# Debugging_board.net
KiCad netlist of a schematic drawn in EasyEDA Pro
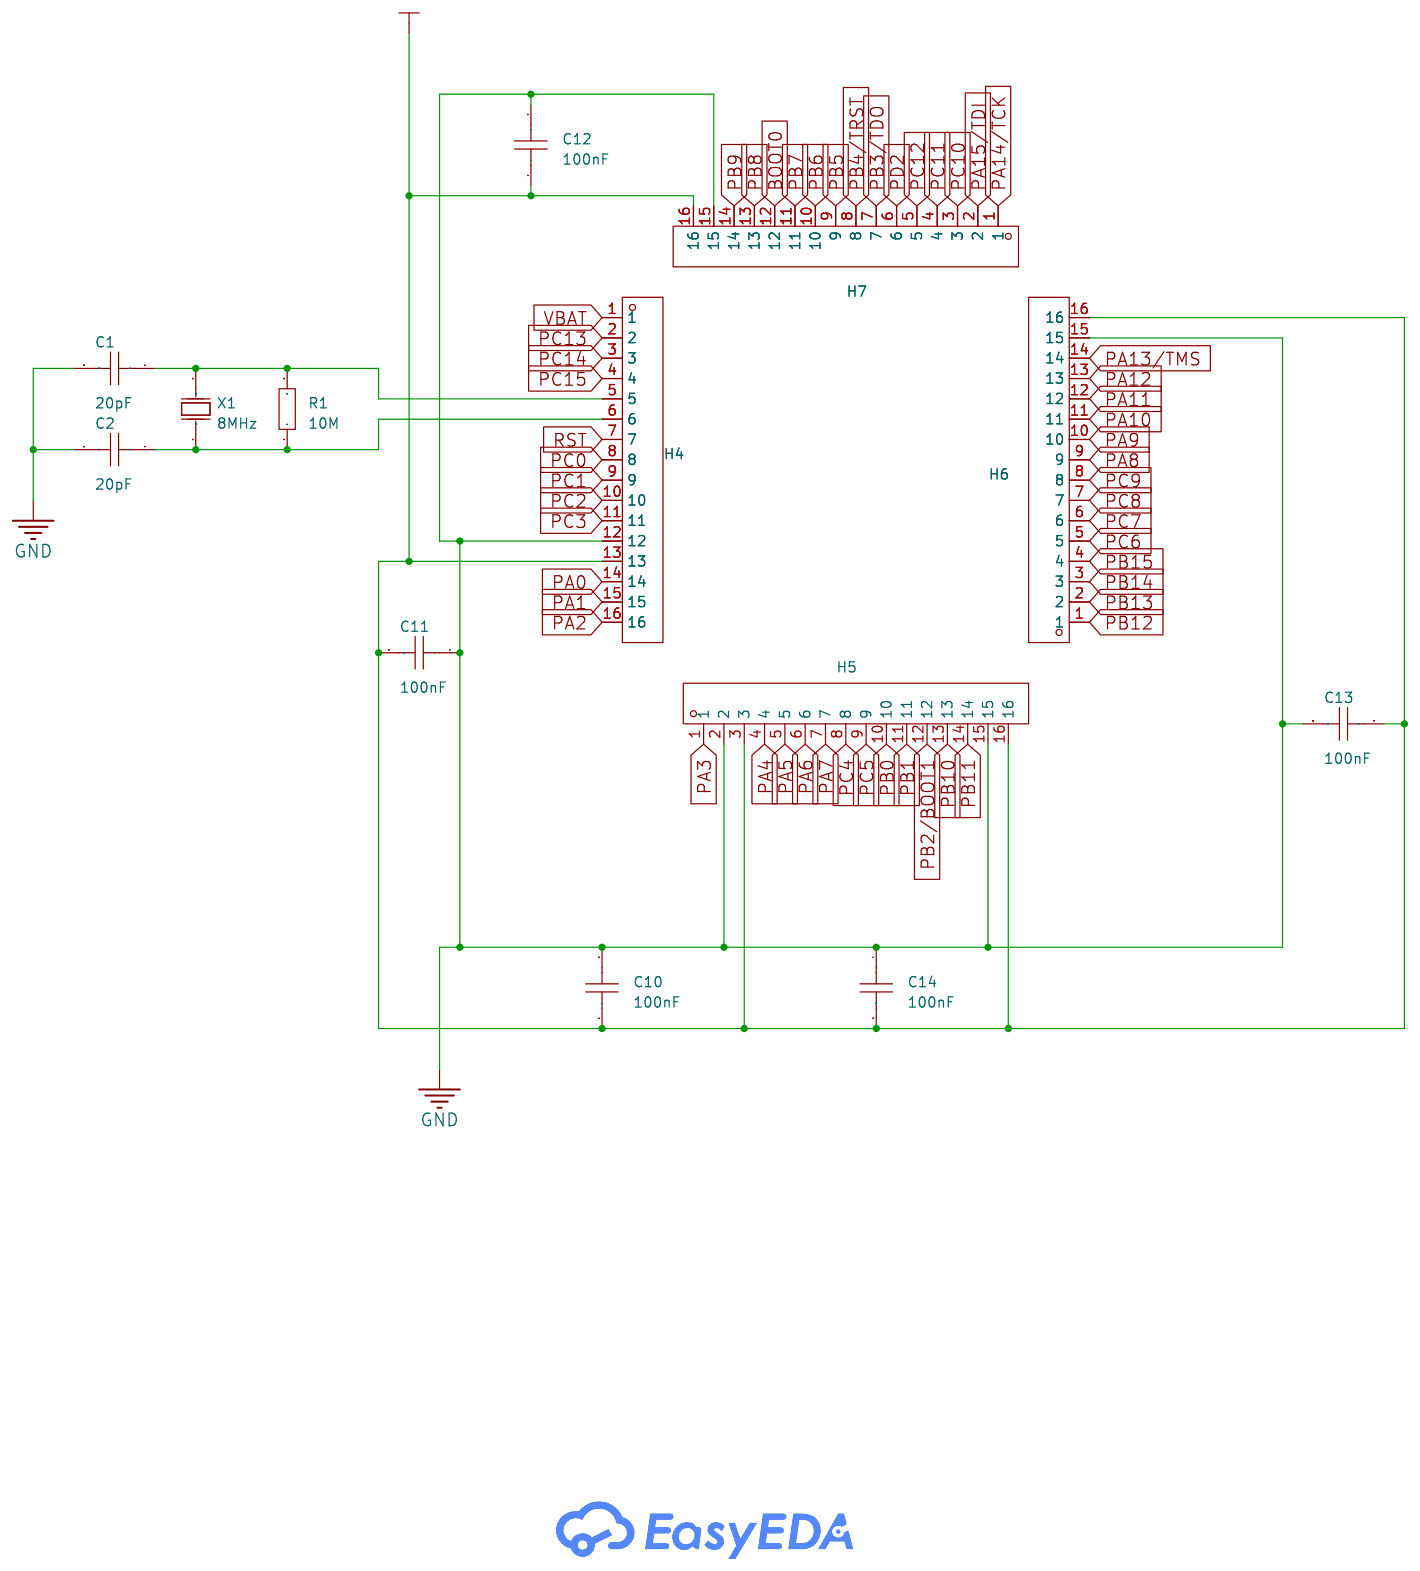
[diagram p0: MC]
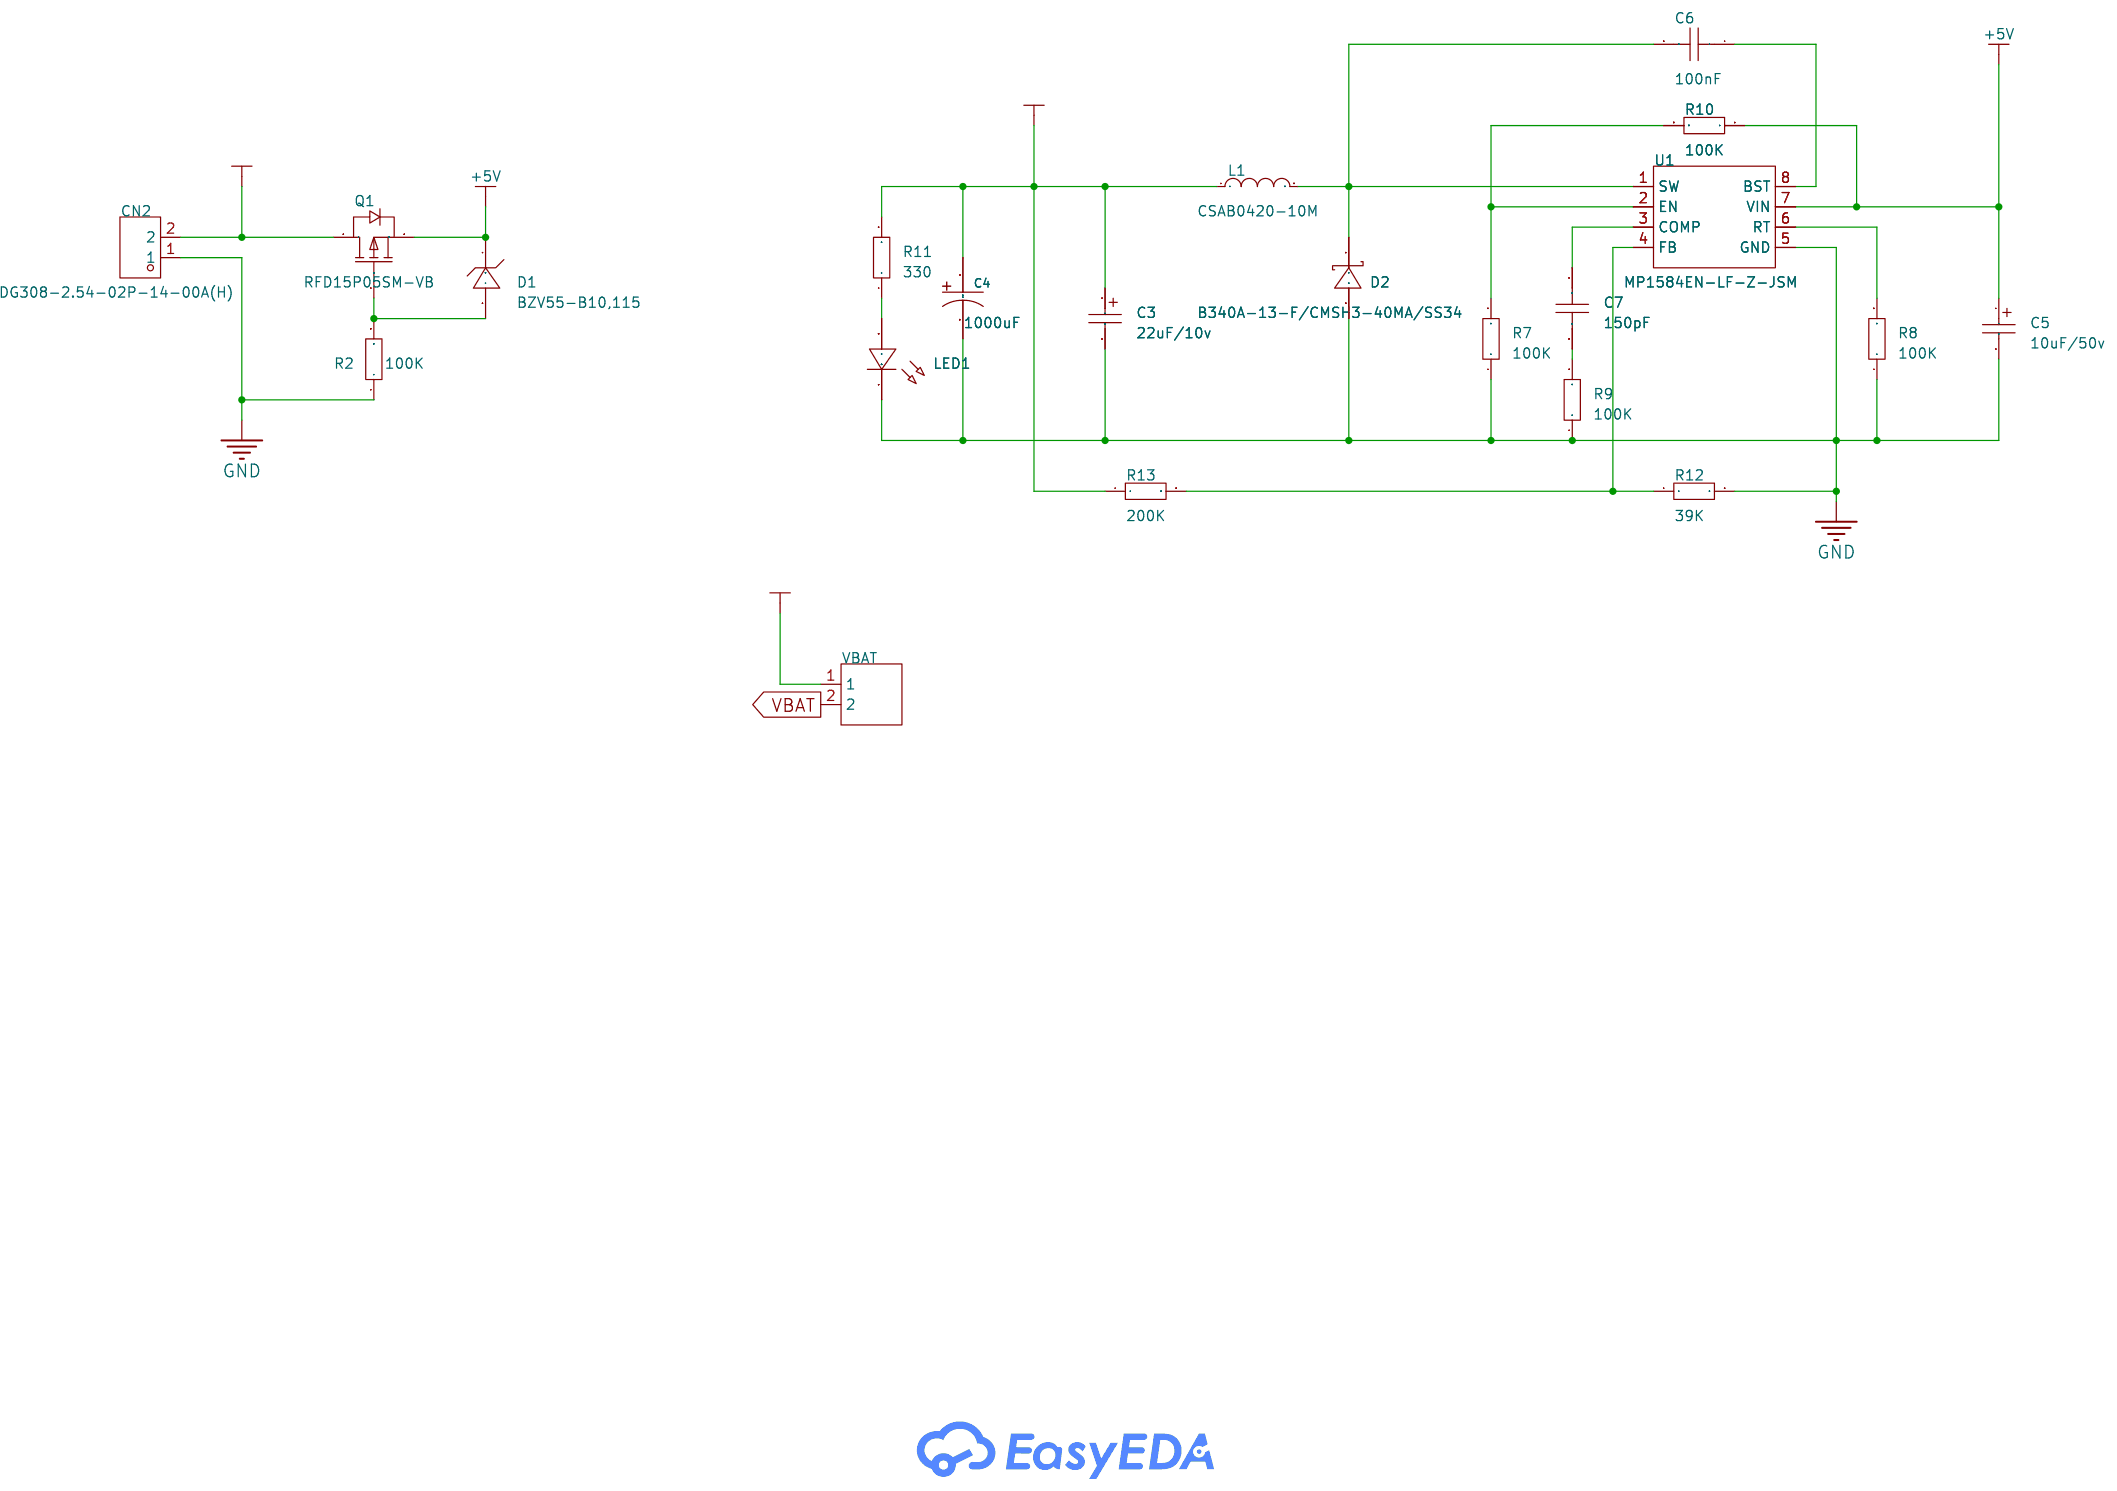
[diagram p1: Power]
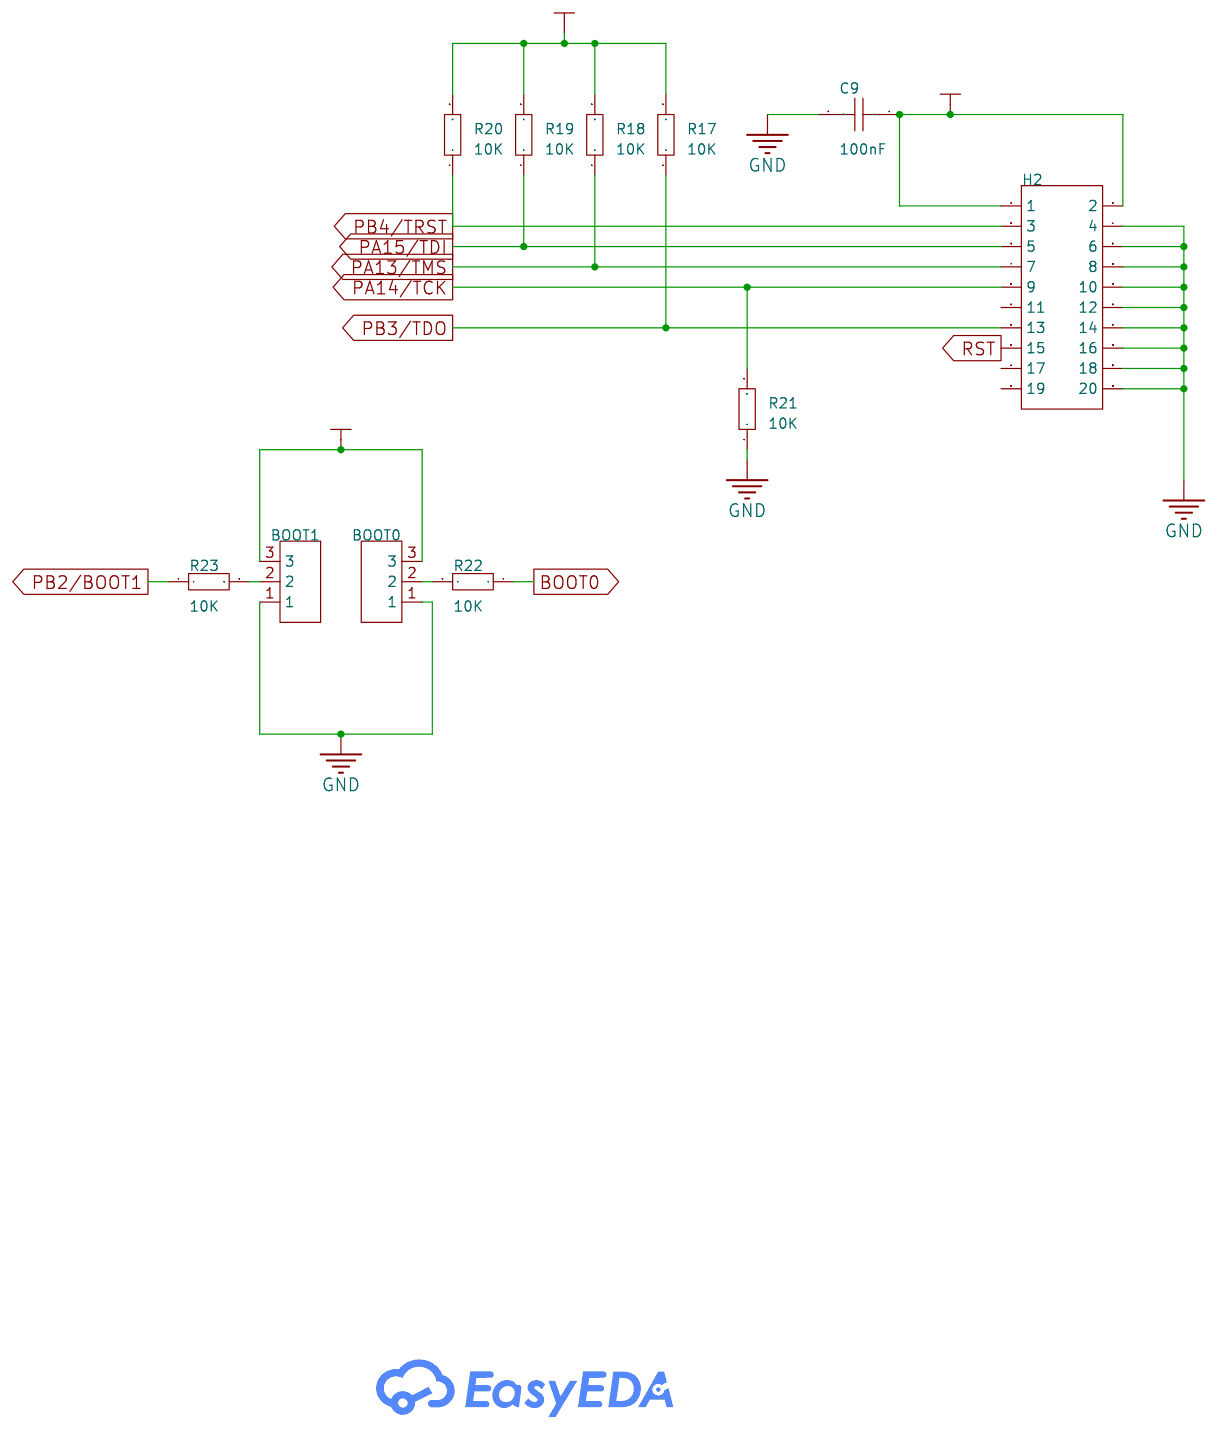
[diagram p2: JTAG/SWD]
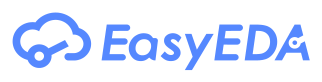
[diagram p3: USB/UART]
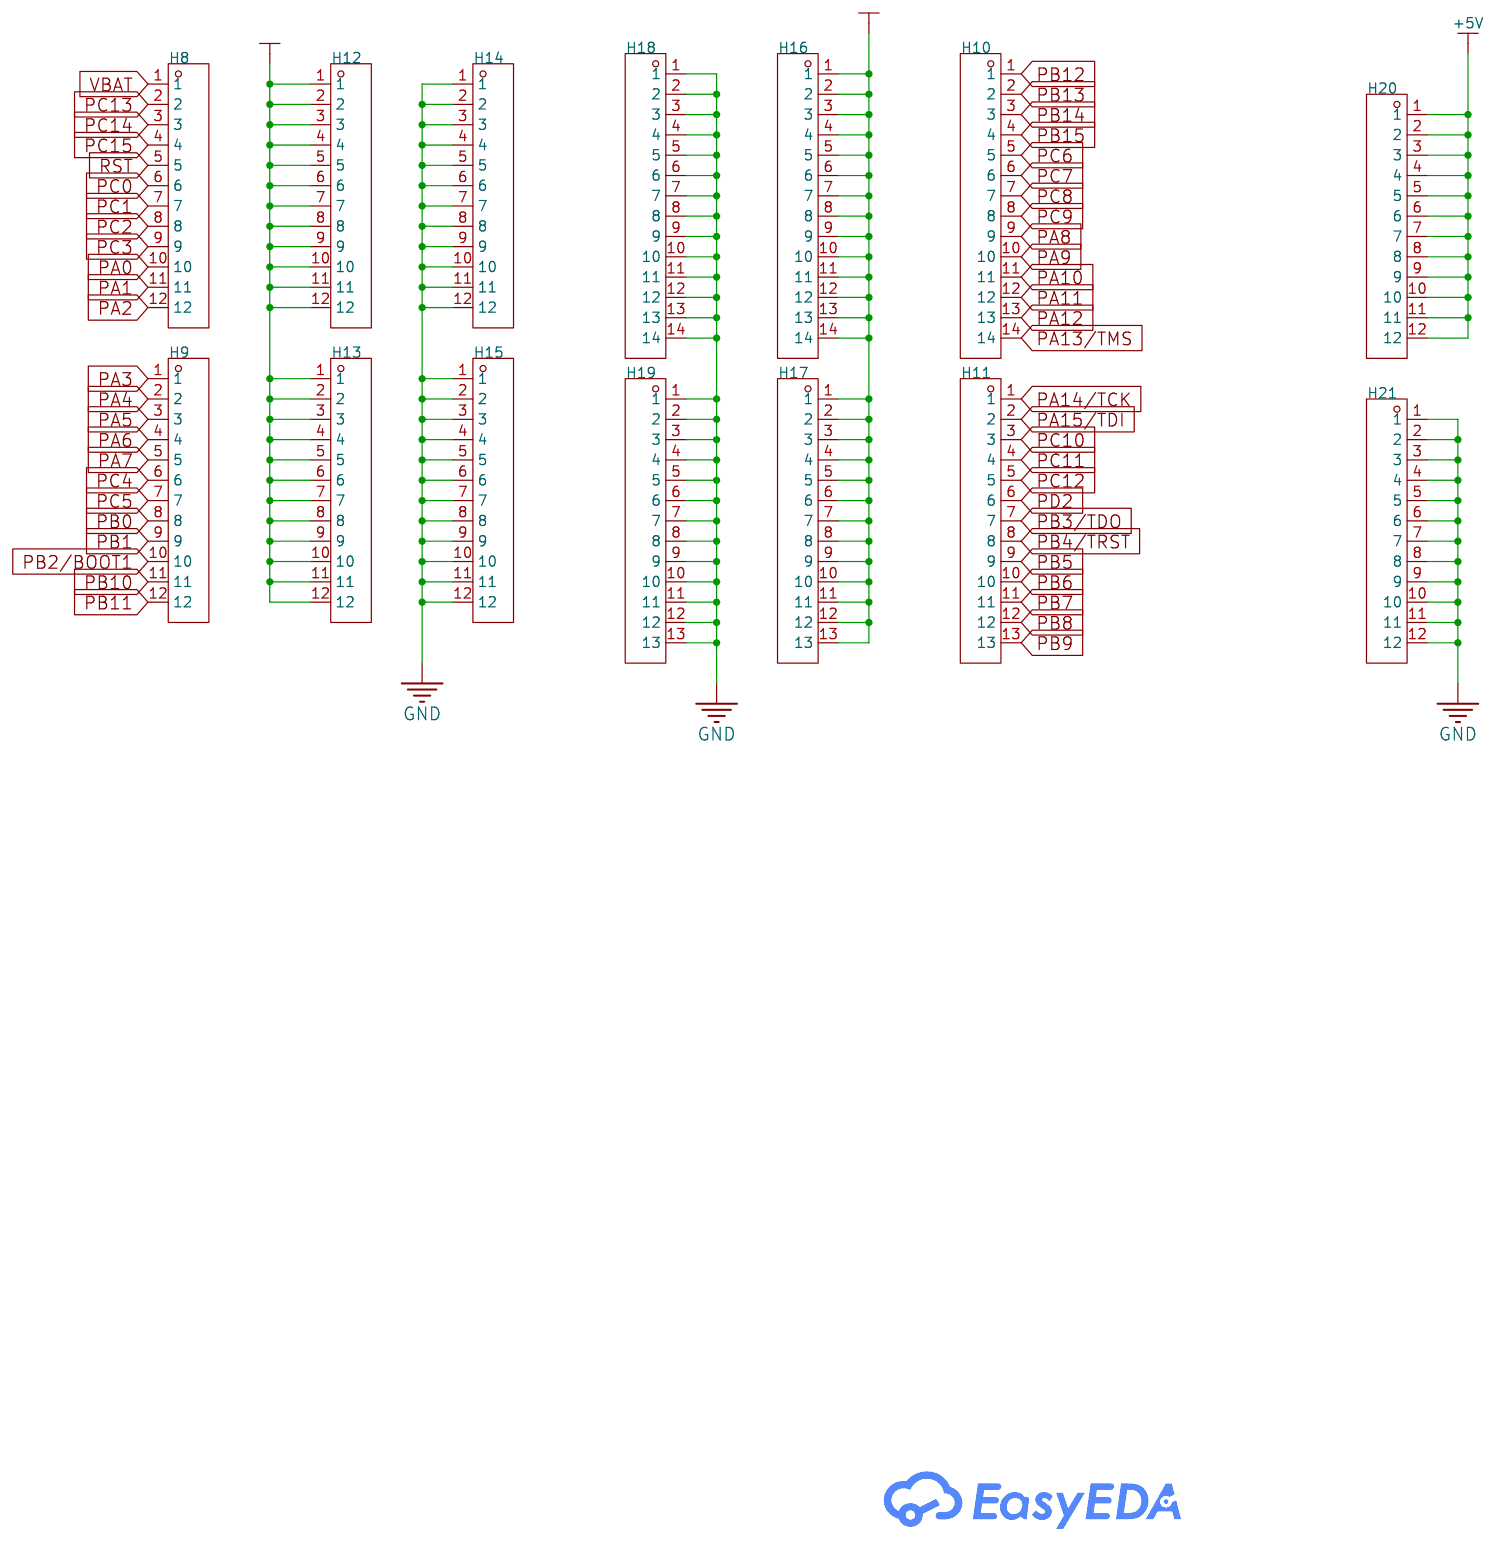
[diagram p4: IN/OUT_Pins]

(export (version "E")
  (design (tool "Eeschema 10.0.6"))
  (components
    (comp (ref "C1")
      (value "20pF")
      (footprint "easyedapro:C0603")
      (libsource (lib "easyedapro") (part "CAP"))
    )
    (comp (ref "C2")
      (value "20pF")
      (footprint "easyedapro:C0603")
      (libsource (lib "easyedapro") (part "CAP"))
    )
    (comp (ref "C10")
      (value "100nF")
      (footprint "easyedapro:C0603")
      (libsource (lib "easyedapro") (part "CAP"))
    )
    (comp (ref "C11")
      (value "100nF")
      (footprint "easyedapro:C0603")
      (libsource (lib "easyedapro") (part "CAP"))
    )
    (comp (ref "C12")
      (value "100nF")
      (footprint "easyedapro:C0603")
      (libsource (lib "easyedapro") (part "CAP"))
    )
    (comp (ref "C13")
      (value "100nF")
      (footprint "easyedapro:C0603")
      (libsource (lib "easyedapro") (part "CAP"))
    )
    (comp (ref "C14")
      (value "100nF")
      (footprint "easyedapro:C0603")
      (libsource (lib "easyedapro") (part "CAP"))
    )
    (comp (ref "H4")
      (value "~")
      (footprint "easyedapro:HDR-TH_16P-P2.54-V-M")
      (libsource (lib "easyedapro") (part "HDR_2.54-1x16P"))
    )
    (comp (ref "H5")
      (value "~")
      (footprint "easyedapro:HDR-TH_16P-P2.54-V-M")
      (libsource (lib "easyedapro") (part "HDR_2.54-1x16P"))
    )
    (comp (ref "H6")
      (value "~")
      (footprint "easyedapro:HDR-TH_16P-P2.54-V-M")
      (libsource (lib "easyedapro") (part "HDR_2.54-1x16P"))
    )
    (comp (ref "H7")
      (value "~")
      (footprint "easyedapro:HDR-TH_16P-P2.54-V-M")
      (libsource (lib "easyedapro") (part "HDR_2.54-1x16P"))
    )
    (comp (ref "R1") (value "10M") (footprint "easyedapro:R0603") (libsource (lib "easyedapro") (part "Res")))
    (comp (ref "X1")
      (value "8MHz")
      (footprint "easyedapro:HC-49S_L11.4-W4.8")
      (fields (field (name "Manufacturer Part") "X49SM8MSD2SI") (field (name "Manufacturer") "YXC(扬兴晶振)"))
      (libsource (lib "easyedapro") (part "X49SM8MSD2SI"))
    )
    (comp (ref "C3")
      (value "22uF/10v")
      (footprint "easyedapro:CAP-SMD_L7.3-W4.3-R-RD")
      (fields (field (name "Manufacturer Part") "T491D106K050AT") (field (name "Manufacturer") "KEMET(基美)"))
      (libsource (lib "easyedapro") (part "T491D106K050AT"))
    )
    (comp (ref "C4")
      (value "1000uF")
      (footprint "easyedapro:CAP-SMD_BD10.0-L10.3-W10.3-LS11.0-FD")
      (fields
        (field (name "Manufacturer Part") "VT1C102MG105000CE0")
        (field (name "Manufacturer") "HUAWEI(华威集团)")
      )
      (libsource (lib "easyedapro") (part "VT1C102MG105000CE0"))
    )
    (comp (ref "C5")
      (value "10uF/50v")
      (footprint "easyedapro:CAP-SMD_L7.3-W4.3-R-RD")
      (fields (field (name "Manufacturer Part") "T491D106K050AT") (field (name "Manufacturer") "KEMET(基美)"))
      (libsource (lib "easyedapro") (part "T491D106K050AT"))
    )
    (comp (ref "C6")
      (value "100nF")
      (footprint "easyedapro:C0603")
      (libsource (lib "easyedapro") (part "CAP"))
    )
    (comp (ref "C7")
      (value "150pF")
      (footprint "easyedapro:C0603")
      (libsource (lib "easyedapro") (part "CAP"))
    )
    (comp (ref "CN2")
      (value "DG308-2.54-02P-14-00A(H)")
      (footprint "easyedapro:CONN-TH_DG308-2.54-02P-14-00A")
      (fields (field (name "Manufacturer") "DEGSON(高正/高松)"))
      (libsource (lib "easyedapro") (part "DG308-2.54-02P-14-00A(H)"))
    )
    (comp (ref "D1")
      (value "BZV55-B10,115")
      (footprint "easyedapro:SOD-80C_L3.3-W1.5-RD")
      (fields (field (name "Manufacturer") "Nexperia(安世)"))
      (libsource (lib "easyedapro") (part "BZV55-B10,115"))
    )
    (comp (ref "D2")
      (value "B340A-13-F/CMSH3-40MA/SS34")
      (footprint "easyedapro:SMA_L4.4-W2.6-LS5.0-RD")
      (fields (field (name "Manufacturer") "DIODES(美台)"))
      (libsource (lib "easyedapro") (part "B340A-13-F"))
    )
    (comp (ref "L1")
      (value "CSAB0420-10M")
      (footprint "easyedapro:IND-SMD_L4.4-W4.2")
      (fields (field (name "Manufacturer") "CODACA(科达嘉)"))
      (libsource (lib "easyedapro") (part "CSAB0420-100M"))
    )
    (comp (ref "LED1")
      (value "~")
      (footprint "easyedapro:LED0805-RD_GREEN")
      (libsource (lib "easyedapro") (part "LED_B"))
    )
    (comp (ref "Q1")
      (value "RFD15P05SM-VB")
      (footprint "easyedapro:TO-252-2_L6.6-W6.1-P4.58-LS9.9-TL")
      (fields (field (name "Manufacturer") "VBsemi(微碧半导体)"))
      (libsource (lib "easyedapro") (part "RFD15P05SM"))
    )
    (comp (ref "R2")
      (value "100K")
      (footprint "easyedapro:R0603")
      (libsource (lib "easyedapro") (part "Res"))
    )
    (comp (ref "R7")
      (value "100K")
      (footprint "easyedapro:R0603")
      (libsource (lib "easyedapro") (part "Res"))
    )
    (comp (ref "R8")
      (value "100K")
      (footprint "easyedapro:R0603")
      (libsource (lib "easyedapro") (part "Res"))
    )
    (comp (ref "R9")
      (value "100K")
      (footprint "easyedapro:R0603")
      (libsource (lib "easyedapro") (part "Res"))
    )
    (comp (ref "R10")
      (value "100K")
      (footprint "easyedapro:R0603")
      (libsource (lib "easyedapro") (part "Res"))
    )
    (comp (ref "R11")
      (value "330")
      (footprint "easyedapro:R0603")
      (libsource (lib "easyedapro") (part "Res"))
    )
    (comp (ref "R12")
      (value "39K")
      (footprint "easyedapro:R0603")
      (libsource (lib "easyedapro") (part "Res"))
    )
    (comp (ref "R13")
      (value "200K")
      (footprint "easyedapro:R0603")
      (libsource (lib "easyedapro") (part "Res"))
    )
    (comp (ref "U1")
      (value "MP1584EN-LF-Z-JSM")
      (footprint "easyedapro:SOP-8_L4.9-W3.9-P1.27-LS6.0-BL_1")
      (fields (field (name "Manufacturer") "JSMSEMI(杰盛微)"))
      (libsource (lib "easyedapro") (part "MP1584EN-LF-Z-JSM"))
    )
    (comp (ref "VBAT")
      (value "~")
      (footprint "easyedapro:HDR-TH_2P-P2.54-V-M-1")
      (libsource (lib "easyedapro") (part "210S-1*2P L=11.6MMGold-plated black"))
    )
    (comp (ref "BOOT0")
      (value "~")
      (footprint "easyedapro:HDR-TH_3P-P2.54-V-M")
      (libsource (lib "easyedapro") (part "PZ254V-11-03P_C2937625"))
    )
    (comp (ref "BOOT1")
      (value "~")
      (footprint "easyedapro:HDR-TH_3P-P2.54-V-M")
      (libsource (lib "easyedapro") (part "PZ254V-11-03P_C2937625"))
    )
    (comp (ref "C9")
      (value "100nF")
      (footprint "easyedapro:C0603")
      (libsource (lib "easyedapro") (part "CAP"))
    )
    (comp (ref "H2")
      (value "~")
      (footprint "easyedapro:HDR-TH_20P-P2.54-V-R2-C10-S2.54")
      (libsource (lib "easyedapro") (part "HDR-F-2.54_2x10"))
    )
    (comp (ref "R17")
      (value "10K")
      (footprint "easyedapro:R0603")
      (libsource (lib "easyedapro") (part "Res"))
    )
    (comp (ref "R18")
      (value "10K")
      (footprint "easyedapro:R0603")
      (libsource (lib "easyedapro") (part "Res"))
    )
    (comp (ref "R19")
      (value "10K")
      (footprint "easyedapro:R0603")
      (libsource (lib "easyedapro") (part "Res"))
    )
    (comp (ref "R20")
      (value "10K")
      (footprint "easyedapro:R0603")
      (libsource (lib "easyedapro") (part "Res"))
    )
    (comp (ref "R21")
      (value "10K")
      (footprint "easyedapro:R0603")
      (libsource (lib "easyedapro") (part "Res"))
    )
    (comp (ref "R22")
      (value "10K")
      (footprint "easyedapro:R0603")
      (libsource (lib "easyedapro") (part "Res"))
    )
    (comp (ref "R23")
      (value "10K")
      (footprint "easyedapro:R0603")
      (libsource (lib "easyedapro") (part "Res"))
    )
    (comp (ref "H8")
      (value "~")
      (footprint "easyedapro:HDR-TH_12P-P2.54-V-M")
      (libsource (lib "easyedapro") (part "HDR_2.54-1x12P"))
    )
    (comp (ref "H9")
      (value "~")
      (footprint "easyedapro:HDR-TH_12P-P2.54-V-M")
      (libsource (lib "easyedapro") (part "HDR_2.54-1x12P"))
    )
    (comp (ref "H10")
      (value "~")
      (footprint "easyedapro:HDR-TH_14P-P2.54-V-M")
      (libsource (lib "easyedapro") (part "HDR_2.54-1x14P"))
    )
    (comp (ref "H11")
      (value "~")
      (footprint "easyedapro:HDR-TH_13P-P2.54-V-M")
      (libsource (lib "easyedapro") (part "HDR_2.54-1x13P"))
    )
    (comp (ref "H12")
      (value "~")
      (footprint "easyedapro:HDR-TH_12P-P2.54-V-M")
      (libsource (lib "easyedapro") (part "HDR_2.54-1x12P"))
    )
    (comp (ref "H13")
      (value "~")
      (footprint "easyedapro:HDR-TH_12P-P2.54-V-M")
      (libsource (lib "easyedapro") (part "HDR_2.54-1x12P"))
    )
    (comp (ref "H14")
      (value "~")
      (footprint "easyedapro:HDR-TH_12P-P2.54-V-M")
      (libsource (lib "easyedapro") (part "HDR_2.54-1x12P"))
    )
    (comp (ref "H15")
      (value "~")
      (footprint "easyedapro:HDR-TH_12P-P2.54-V-M")
      (libsource (lib "easyedapro") (part "HDR_2.54-1x12P"))
    )
    (comp (ref "H16")
      (value "~")
      (footprint "easyedapro:HDR-TH_14P-P2.54-V-M")
      (libsource (lib "easyedapro") (part "HDR_2.54-1x14P"))
    )
    (comp (ref "H17")
      (value "~")
      (footprint "easyedapro:HDR-TH_13P-P2.54-V-M")
      (libsource (lib "easyedapro") (part "HDR_2.54-1x13P"))
    )
    (comp (ref "H18")
      (value "~")
      (footprint "easyedapro:HDR-TH_14P-P2.54-V-M")
      (libsource (lib "easyedapro") (part "HDR_2.54-1x14P"))
    )
    (comp (ref "H19")
      (value "~")
      (footprint "easyedapro:HDR-TH_13P-P2.54-V-M")
      (libsource (lib "easyedapro") (part "HDR_2.54-1x13P"))
    )
    (comp (ref "H20")
      (value "~")
      (footprint "easyedapro:HDR-TH_12P-P2.54-V-M")
      (libsource (lib "easyedapro") (part "HDR_2.54-1x12P"))
    )
    (comp (ref "H21")
      (value "~")
      (footprint "easyedapro:HDR-TH_12P-P2.54-V-M")
      (libsource (lib "easyedapro") (part "HDR_2.54-1x12P"))
    )
  )
  (nets
    (net (code "1") (name "+3V3") (class "Default")
      (node (ref "BOOT0") (pin "3") (pinfunction "3_3") (pintype "unspecified"))
      (node (ref "BOOT1") (pin "3") (pinfunction "3_3") (pintype "unspecified"))
      (node (ref "C10") (pin "1") (pinfunction "1_1") (pintype "input"))
      (node (ref "C11") (pin "2") (pinfunction "2_2") (pintype "input"))
      (node (ref "C12") (pin "1") (pinfunction "1_1") (pintype "input"))
      (node (ref "C13") (pin "1") (pinfunction "1_1") (pintype "input"))
      (node (ref "C14") (pin "2") (pinfunction "2_2") (pintype "input"))
      (node (ref "C3") (pin "1") (pinfunction "1_1") (pintype "input"))
      (node (ref "C4") (pin "1") (pinfunction "1_1") (pintype "input"))
      (node (ref "C9") (pin "1") (pinfunction "1_1") (pintype "input"))
      (node (ref "H12") (pin "1") (pinfunction "1_1") (pintype "input"))
      (node (ref "H12") (pin "10") (pinfunction "10_10") (pintype "input"))
      (node (ref "H12") (pin "11") (pinfunction "11_11") (pintype "input"))
      (node (ref "H12") (pin "12") (pinfunction "12_12") (pintype "input"))
      (node (ref "H12") (pin "2") (pinfunction "2_2") (pintype "input"))
      (node (ref "H12") (pin "3") (pinfunction "3_3") (pintype "input"))
      (node (ref "H12") (pin "4") (pinfunction "4_4") (pintype "input"))
      (node (ref "H12") (pin "5") (pinfunction "5_5") (pintype "input"))
      (node (ref "H12") (pin "6") (pinfunction "6_6") (pintype "input"))
      (node (ref "H12") (pin "7") (pinfunction "7_7") (pintype "input"))
      (node (ref "H12") (pin "8") (pinfunction "8_8") (pintype "input"))
      (node (ref "H12") (pin "9") (pinfunction "9_9") (pintype "input"))
      (node (ref "H13") (pin "1") (pinfunction "1_1") (pintype "input"))
      (node (ref "H13") (pin "10") (pinfunction "10_10") (pintype "input"))
      (node (ref "H13") (pin "11") (pinfunction "11_11") (pintype "input"))
      (node (ref "H13") (pin "12") (pinfunction "12_12") (pintype "input"))
      (node (ref "H13") (pin "2") (pinfunction "2_2") (pintype "input"))
      (node (ref "H13") (pin "3") (pinfunction "3_3") (pintype "input"))
      (node (ref "H13") (pin "4") (pinfunction "4_4") (pintype "input"))
      (node (ref "H13") (pin "5") (pinfunction "5_5") (pintype "input"))
      (node (ref "H13") (pin "6") (pinfunction "6_6") (pintype "input"))
      (node (ref "H13") (pin "7") (pinfunction "7_7") (pintype "input"))
      (node (ref "H13") (pin "8") (pinfunction "8_8") (pintype "input"))
      (node (ref "H13") (pin "9") (pinfunction "9_9") (pintype "input"))
      (node (ref "H16") (pin "1") (pinfunction "1_1") (pintype "input"))
      (node (ref "H16") (pin "10") (pinfunction "10_10") (pintype "input"))
      (node (ref "H16") (pin "11") (pinfunction "11_11") (pintype "input"))
      (node (ref "H16") (pin "12") (pinfunction "12_12") (pintype "input"))
      (node (ref "H16") (pin "13") (pinfunction "13_13") (pintype "input"))
      (node (ref "H16") (pin "14") (pinfunction "14_14") (pintype "input"))
      (node (ref "H16") (pin "2") (pinfunction "2_2") (pintype "input"))
      (node (ref "H16") (pin "3") (pinfunction "3_3") (pintype "input"))
      (node (ref "H16") (pin "4") (pinfunction "4_4") (pintype "input"))
      (node (ref "H16") (pin "5") (pinfunction "5_5") (pintype "input"))
      (node (ref "H16") (pin "6") (pinfunction "6_6") (pintype "input"))
      (node (ref "H16") (pin "7") (pinfunction "7_7") (pintype "input"))
      (node (ref "H16") (pin "8") (pinfunction "8_8") (pintype "input"))
      (node (ref "H16") (pin "9") (pinfunction "9_9") (pintype "input"))
      (node (ref "H17") (pin "1") (pinfunction "1_1") (pintype "input"))
      (node (ref "H17") (pin "10") (pinfunction "10_10") (pintype "input"))
      (node (ref "H17") (pin "11") (pinfunction "11_11") (pintype "input"))
      (node (ref "H17") (pin "12") (pinfunction "12_12") (pintype "input"))
      (node (ref "H17") (pin "13") (pinfunction "13_13") (pintype "input"))
      (node (ref "H17") (pin "2") (pinfunction "2_2") (pintype "input"))
      (node (ref "H17") (pin "3") (pinfunction "3_3") (pintype "input"))
      (node (ref "H17") (pin "4") (pinfunction "4_4") (pintype "input"))
      (node (ref "H17") (pin "5") (pinfunction "5_5") (pintype "input"))
      (node (ref "H17") (pin "6") (pinfunction "6_6") (pintype "input"))
      (node (ref "H17") (pin "7") (pinfunction "7_7") (pintype "input"))
      (node (ref "H17") (pin "8") (pinfunction "8_8") (pintype "input"))
      (node (ref "H17") (pin "9") (pinfunction "9_9") (pintype "input"))
      (node (ref "H2") (pin "1") (pinfunction "1_1") (pintype "input"))
      (node (ref "H2") (pin "2") (pinfunction "2_2") (pintype "input"))
      (node (ref "H4") (pin "13") (pinfunction "13_13") (pintype "input"))
      (node (ref "H5") (pin "16") (pinfunction "16_16") (pintype "input"))
      (node (ref "H5") (pin "3") (pinfunction "3_3") (pintype "input"))
      (node (ref "H6") (pin "16") (pinfunction "16_16") (pintype "input"))
      (node (ref "H7") (pin "16") (pinfunction "16_16") (pintype "input"))
      (node (ref "L1") (pin "1") (pinfunction "1_1") (pintype "unspecified"))
      (node (ref "R11") (pin "2") (pinfunction "2_2") (pintype "input"))
      (node (ref "R13") (pin "1") (pinfunction "1_1") (pintype "input"))
      (node (ref "R17") (pin "2") (pinfunction "2_2") (pintype "input"))
      (node (ref "R18") (pin "2") (pinfunction "2_2") (pintype "input"))
      (node (ref "R19") (pin "2") (pinfunction "2_2") (pintype "input"))
      (node (ref "R20") (pin "2") (pinfunction "2_2") (pintype "input"))
      (node (ref "VBAT") (pin "1") (pinfunction "1_1") (pintype "unspecified"))
    )
    (net (code "2") (name "+5V") (class "Default")
      (node (ref "C5") (pin "1") (pinfunction "1_1") (pintype "input"))
      (node (ref "D1") (pin "1") (pinfunction "C_1") (pintype "unspecified"))
      (node (ref "H20") (pin "1") (pinfunction "1_1") (pintype "input"))
      (node (ref "H20") (pin "10") (pinfunction "10_10") (pintype "input"))
      (node (ref "H20") (pin "11") (pinfunction "11_11") (pintype "input"))
      (node (ref "H20") (pin "12") (pinfunction "12_12") (pintype "input"))
      (node (ref "H20") (pin "2") (pinfunction "2_2") (pintype "input"))
      (node (ref "H20") (pin "3") (pinfunction "3_3") (pintype "input"))
      (node (ref "H20") (pin "4") (pinfunction "4_4") (pintype "input"))
      (node (ref "H20") (pin "5") (pinfunction "5_5") (pintype "input"))
      (node (ref "H20") (pin "6") (pinfunction "6_6") (pintype "input"))
      (node (ref "H20") (pin "7") (pinfunction "7_7") (pintype "input"))
      (node (ref "H20") (pin "8") (pinfunction "8_8") (pintype "input"))
      (node (ref "H20") (pin "9") (pinfunction "9_9") (pintype "input"))
      (node (ref "Q1") (pin "3") (pinfunction "S_3") (pintype "unspecified"))
      (node (ref "R10") (pin "1") (pinfunction "1_1") (pintype "input"))
      (node (ref "U1") (pin "7") (pinfunction "VIN_7") (pintype "unspecified"))
    )
    (net (code "3") (name "+12V") (class "Default")
      (node (ref "CN2") (pin "2") (pinfunction "2_2") (pintype "unspecified"))
      (node (ref "Q1") (pin "2") (pinfunction "D_2") (pintype "unspecified"))
    )
    (net (code "4") (name "BOOT0") (class "Default")
      (node (ref "H7") (pin "12") (pinfunction "12_12") (pintype "input"))
      (node (ref "R22") (pin "1") (pinfunction "1_1") (pintype "input"))
    )
    (net (code "5") (name "GND") (class "Default")
      (node (ref "BOOT0") (pin "1") (pinfunction "1_1") (pintype "unspecified"))
      (node (ref "BOOT1") (pin "1") (pinfunction "1_1") (pintype "unspecified"))
      (node (ref "C1") (pin "2") (pinfunction "2_2") (pintype "input"))
      (node (ref "C10") (pin "2") (pinfunction "2_2") (pintype "input"))
      (node (ref "C11") (pin "1") (pinfunction "1_1") (pintype "input"))
      (node (ref "C12") (pin "2") (pinfunction "2_2") (pintype "input"))
      (node (ref "C13") (pin "2") (pinfunction "2_2") (pintype "input"))
      (node (ref "C14") (pin "1") (pinfunction "1_1") (pintype "input"))
      (node (ref "C2") (pin "2") (pinfunction "2_2") (pintype "input"))
      (node (ref "C3") (pin "2") (pinfunction "2_2") (pintype "input"))
      (node (ref "C4") (pin "2") (pinfunction "2_2") (pintype "input"))
      (node (ref "C5") (pin "2") (pinfunction "2_2") (pintype "input"))
      (node (ref "C9") (pin "2") (pinfunction "2_2") (pintype "input"))
      (node (ref "CN2") (pin "1") (pinfunction "1_1") (pintype "unspecified"))
      (node (ref "D2") (pin "2") (pinfunction "A_2") (pintype "unspecified"))
      (node (ref "H14") (pin "1") (pinfunction "1_1") (pintype "input"))
      (node (ref "H14") (pin "10") (pinfunction "10_10") (pintype "input"))
      (node (ref "H14") (pin "11") (pinfunction "11_11") (pintype "input"))
      (node (ref "H14") (pin "12") (pinfunction "12_12") (pintype "input"))
      (node (ref "H14") (pin "2") (pinfunction "2_2") (pintype "input"))
      (node (ref "H14") (pin "3") (pinfunction "3_3") (pintype "input"))
      (node (ref "H14") (pin "4") (pinfunction "4_4") (pintype "input"))
      (node (ref "H14") (pin "5") (pinfunction "5_5") (pintype "input"))
      (node (ref "H14") (pin "6") (pinfunction "6_6") (pintype "input"))
      (node (ref "H14") (pin "7") (pinfunction "7_7") (pintype "input"))
      (node (ref "H14") (pin "8") (pinfunction "8_8") (pintype "input"))
      (node (ref "H14") (pin "9") (pinfunction "9_9") (pintype "input"))
      (node (ref "H15") (pin "1") (pinfunction "1_1") (pintype "input"))
      (node (ref "H15") (pin "10") (pinfunction "10_10") (pintype "input"))
      (node (ref "H15") (pin "11") (pinfunction "11_11") (pintype "input"))
      (node (ref "H15") (pin "12") (pinfunction "12_12") (pintype "input"))
      (node (ref "H15") (pin "2") (pinfunction "2_2") (pintype "input"))
      (node (ref "H15") (pin "3") (pinfunction "3_3") (pintype "input"))
      (node (ref "H15") (pin "4") (pinfunction "4_4") (pintype "input"))
      (node (ref "H15") (pin "5") (pinfunction "5_5") (pintype "input"))
      (node (ref "H15") (pin "6") (pinfunction "6_6") (pintype "input"))
      (node (ref "H15") (pin "7") (pinfunction "7_7") (pintype "input"))
      (node (ref "H15") (pin "8") (pinfunction "8_8") (pintype "input"))
      (node (ref "H15") (pin "9") (pinfunction "9_9") (pintype "input"))
      (node (ref "H18") (pin "1") (pinfunction "1_1") (pintype "input"))
      (node (ref "H18") (pin "10") (pinfunction "10_10") (pintype "input"))
      (node (ref "H18") (pin "11") (pinfunction "11_11") (pintype "input"))
      (node (ref "H18") (pin "12") (pinfunction "12_12") (pintype "input"))
      (node (ref "H18") (pin "13") (pinfunction "13_13") (pintype "input"))
      (node (ref "H18") (pin "14") (pinfunction "14_14") (pintype "input"))
      (node (ref "H18") (pin "2") (pinfunction "2_2") (pintype "input"))
      (node (ref "H18") (pin "3") (pinfunction "3_3") (pintype "input"))
      (node (ref "H18") (pin "4") (pinfunction "4_4") (pintype "input"))
      (node (ref "H18") (pin "5") (pinfunction "5_5") (pintype "input"))
      (node (ref "H18") (pin "6") (pinfunction "6_6") (pintype "input"))
      (node (ref "H18") (pin "7") (pinfunction "7_7") (pintype "input"))
      (node (ref "H18") (pin "8") (pinfunction "8_8") (pintype "input"))
      (node (ref "H18") (pin "9") (pinfunction "9_9") (pintype "input"))
      (node (ref "H19") (pin "1") (pinfunction "1_1") (pintype "input"))
      (node (ref "H19") (pin "10") (pinfunction "10_10") (pintype "input"))
      (node (ref "H19") (pin "11") (pinfunction "11_11") (pintype "input"))
      (node (ref "H19") (pin "12") (pinfunction "12_12") (pintype "input"))
      (node (ref "H19") (pin "13") (pinfunction "13_13") (pintype "input"))
      (node (ref "H19") (pin "2") (pinfunction "2_2") (pintype "input"))
      (node (ref "H19") (pin "3") (pinfunction "3_3") (pintype "input"))
      (node (ref "H19") (pin "4") (pinfunction "4_4") (pintype "input"))
      (node (ref "H19") (pin "5") (pinfunction "5_5") (pintype "input"))
      (node (ref "H19") (pin "6") (pinfunction "6_6") (pintype "input"))
      (node (ref "H19") (pin "7") (pinfunction "7_7") (pintype "input"))
      (node (ref "H19") (pin "8") (pinfunction "8_8") (pintype "input"))
      (node (ref "H19") (pin "9") (pinfunction "9_9") (pintype "input"))
      (node (ref "H2") (pin "10") (pinfunction "10_10") (pintype "input"))
      (node (ref "H2") (pin "12") (pinfunction "12_12") (pintype "input"))
      (node (ref "H2") (pin "14") (pinfunction "14_14") (pintype "input"))
      (node (ref "H2") (pin "16") (pinfunction "16_16") (pintype "input"))
      (node (ref "H2") (pin "18") (pinfunction "18_18") (pintype "input"))
      (node (ref "H2") (pin "20") (pinfunction "20_20") (pintype "input"))
      (node (ref "H2") (pin "4") (pinfunction "4_4") (pintype "input"))
      (node (ref "H2") (pin "6") (pinfunction "6_6") (pintype "input"))
      (node (ref "H2") (pin "8") (pinfunction "8_8") (pintype "input"))
      (node (ref "H21") (pin "1") (pinfunction "1_1") (pintype "input"))
      (node (ref "H21") (pin "10") (pinfunction "10_10") (pintype "input"))
      (node (ref "H21") (pin "11") (pinfunction "11_11") (pintype "input"))
      (node (ref "H21") (pin "12") (pinfunction "12_12") (pintype "input"))
      (node (ref "H21") (pin "2") (pinfunction "2_2") (pintype "input"))
      (node (ref "H21") (pin "3") (pinfunction "3_3") (pintype "input"))
      (node (ref "H21") (pin "4") (pinfunction "4_4") (pintype "input"))
      (node (ref "H21") (pin "5") (pinfunction "5_5") (pintype "input"))
      (node (ref "H21") (pin "6") (pinfunction "6_6") (pintype "input"))
      (node (ref "H21") (pin "7") (pinfunction "7_7") (pintype "input"))
      (node (ref "H21") (pin "8") (pinfunction "8_8") (pintype "input"))
      (node (ref "H21") (pin "9") (pinfunction "9_9") (pintype "input"))
      (node (ref "H4") (pin "12") (pinfunction "12_12") (pintype "input"))
      (node (ref "H5") (pin "15") (pinfunction "15_15") (pintype "input"))
      (node (ref "H5") (pin "2") (pinfunction "2_2") (pintype "input"))
      (node (ref "H6") (pin "15") (pinfunction "15_15") (pintype "input"))
      (node (ref "H7") (pin "15") (pinfunction "15_15") (pintype "input"))
      (node (ref "LED1") (pin "1") (pinfunction "C_1") (pintype "input"))
      (node (ref "R12") (pin "2") (pinfunction "2_2") (pintype "input"))
      (node (ref "R2") (pin "1") (pinfunction "1_1") (pintype "input"))
      (node (ref "R21") (pin "1") (pinfunction "1_1") (pintype "input"))
      (node (ref "R7") (pin "1") (pinfunction "1_1") (pintype "input"))
      (node (ref "R8") (pin "1") (pinfunction "1_1") (pintype "input"))
      (node (ref "R9") (pin "1") (pinfunction "1_1") (pintype "input"))
      (node (ref "U1") (pin "5") (pinfunction "GND_5") (pintype "unspecified"))
    )
    (net (code "6") (name "Net-(BOOT0-Pad2)") (class "Default")
      (node (ref "BOOT0") (pin "2") (pinfunction "2_2") (pintype "unspecified"))
      (node (ref "R22") (pin "2") (pinfunction "2_2") (pintype "input"))
    )
    (net (code "7") (name "Net-(BOOT1-Pad2)") (class "Default")
      (node (ref "BOOT1") (pin "2") (pinfunction "2_2") (pintype "unspecified"))
      (node (ref "R23") (pin "2") (pinfunction "2_2") (pintype "input"))
    )
    (net (code "8") (name "Net-(C7-Pad2)") (class "Default")
      (node (ref "C7") (pin "2") (pinfunction "2_2") (pintype "input"))
      (node (ref "R9") (pin "2") (pinfunction "2_2") (pintype "input"))
    )
    (net (code "9") (name "Net-(D1-A)") (class "Default")
      (node (ref "D1") (pin "2") (pinfunction "A_2") (pintype "unspecified"))
      (node (ref "Q1") (pin "1") (pinfunction "G_1") (pintype "unspecified"))
      (node (ref "R2") (pin "2") (pinfunction "2_2") (pintype "input"))
    )
    (net (code "10") (name "Net-(D2-K)") (class "Default")
      (node (ref "C6") (pin "2") (pinfunction "2_2") (pintype "input"))
      (node (ref "D2") (pin "1") (pinfunction "K_1") (pintype "unspecified"))
      (node (ref "L1") (pin "2") (pinfunction "2_2") (pintype "unspecified"))
      (node (ref "U1") (pin "1") (pinfunction "SW_1") (pintype "unspecified"))
    )
    (net (code "11") (name "Net-(LED1-A)") (class "Default")
      (node (ref "LED1") (pin "2") (pinfunction "A_2") (pintype "input"))
      (node (ref "R11") (pin "1") (pinfunction "1_1") (pintype "input"))
    )
    (net (code "12") (name "Net-(U1-BST)") (class "Default")
      (node (ref "C6") (pin "1") (pinfunction "1_1") (pintype "input"))
      (node (ref "U1") (pin "8") (pinfunction "BST_8") (pintype "unspecified"))
    )
    (net (code "13") (name "Net-(U1-COMP)") (class "Default")
      (node (ref "C7") (pin "1") (pinfunction "1_1") (pintype "input"))
      (node (ref "U1") (pin "3") (pinfunction "COMP_3") (pintype "unspecified"))
    )
    (net (code "14") (name "Net-(U1-EN)") (class "Default")
      (node (ref "R10") (pin "2") (pinfunction "2_2") (pintype "input"))
      (node (ref "R7") (pin "2") (pinfunction "2_2") (pintype "input"))
      (node (ref "U1") (pin "2") (pinfunction "EN_2") (pintype "unspecified"))
    )
    (net (code "15") (name "Net-(U1-FB)") (class "Default")
      (node (ref "R12") (pin "1") (pinfunction "1_1") (pintype "input"))
      (node (ref "R13") (pin "2") (pinfunction "2_2") (pintype "input"))
      (node (ref "U1") (pin "4") (pinfunction "FB_4") (pintype "unspecified"))
    )
    (net (code "16") (name "Net-(U1-RT)") (class "Default")
      (node (ref "R8") (pin "2") (pinfunction "2_2") (pintype "input"))
      (node (ref "U1") (pin "6") (pinfunction "RT_6") (pintype "unspecified"))
    )
    (net (code "17") (name "Net-(X1-OSC1)") (class "Default")
      (node (ref "C2") (pin "1") (pinfunction "1_1") (pintype "input"))
      (node (ref "H4") (pin "6") (pinfunction "6_6") (pintype "input"))
      (node (ref "R1") (pin "1") (pinfunction "1_1") (pintype "input"))
      (node (ref "X1") (pin "1") (pinfunction "OSC1_1") (pintype "input"))
    )
    (net (code "18") (name "Net-(X1-OSC2)") (class "Default")
      (node (ref "C1") (pin "1") (pinfunction "1_1") (pintype "input"))
      (node (ref "H4") (pin "5") (pinfunction "5_5") (pintype "input"))
      (node (ref "R1") (pin "2") (pinfunction "2_2") (pintype "input"))
      (node (ref "X1") (pin "2") (pinfunction "OSC2_2") (pintype "input"))
    )
    (net (code "19") (name "PA0") (class "Default")
      (node (ref "H4") (pin "14") (pinfunction "14_14") (pintype "input"))
      (node (ref "H8") (pin "10") (pinfunction "10_10") (pintype "input"))
    )
    (net (code "20") (name "PA1") (class "Default")
      (node (ref "H4") (pin "15") (pinfunction "15_15") (pintype "input"))
      (node (ref "H8") (pin "11") (pinfunction "11_11") (pintype "input"))
    )
    (net (code "21") (name "PA2") (class "Default")
      (node (ref "H4") (pin "16") (pinfunction "16_16") (pintype "input"))
      (node (ref "H8") (pin "12") (pinfunction "12_12") (pintype "input"))
    )
    (net (code "22") (name "PA3") (class "Default")
      (node (ref "H5") (pin "1") (pinfunction "1_1") (pintype "input"))
      (node (ref "H9") (pin "1") (pinfunction "1_1") (pintype "input"))
    )
    (net (code "23") (name "PA4") (class "Default")
      (node (ref "H5") (pin "4") (pinfunction "4_4") (pintype "input"))
      (node (ref "H9") (pin "2") (pinfunction "2_2") (pintype "input"))
    )
    (net (code "24") (name "PA5") (class "Default")
      (node (ref "H5") (pin "5") (pinfunction "5_5") (pintype "input"))
      (node (ref "H9") (pin "3") (pinfunction "3_3") (pintype "input"))
    )
    (net (code "25") (name "PA6") (class "Default")
      (node (ref "H5") (pin "6") (pinfunction "6_6") (pintype "input"))
      (node (ref "H9") (pin "4") (pinfunction "4_4") (pintype "input"))
    )
    (net (code "26") (name "PA7") (class "Default")
      (node (ref "H5") (pin "7") (pinfunction "7_7") (pintype "input"))
      (node (ref "H9") (pin "5") (pinfunction "5_5") (pintype "input"))
    )
    (net (code "27") (name "PA8") (class "Default")
      (node (ref "H10") (pin "9") (pinfunction "9_9") (pintype "input"))
      (node (ref "H6") (pin "9") (pinfunction "9_9") (pintype "input"))
    )
    (net (code "28") (name "PA9") (class "Default")
      (node (ref "H10") (pin "10") (pinfunction "10_10") (pintype "input"))
      (node (ref "H6") (pin "10") (pinfunction "10_10") (pintype "input"))
    )
    (net (code "29") (name "PA10") (class "Default")
      (node (ref "H10") (pin "11") (pinfunction "11_11") (pintype "input"))
      (node (ref "H6") (pin "11") (pinfunction "11_11") (pintype "input"))
    )
    (net (code "30") (name "PA11") (class "Default")
      (node (ref "H10") (pin "12") (pinfunction "12_12") (pintype "input"))
      (node (ref "H6") (pin "12") (pinfunction "12_12") (pintype "input"))
    )
    (net (code "31") (name "PA12") (class "Default")
      (node (ref "H10") (pin "13") (pinfunction "13_13") (pintype "input"))
      (node (ref "H6") (pin "13") (pinfunction "13_13") (pintype "input"))
    )
    (net (code "32") (name "PA13{slash}TMS") (class "Default")
      (node (ref "H10") (pin "14") (pinfunction "14_14") (pintype "input"))
      (node (ref "H2") (pin "7") (pinfunction "7_7") (pintype "input"))
      (node (ref "H6") (pin "14") (pinfunction "14_14") (pintype "input"))
      (node (ref "R18") (pin "1") (pinfunction "1_1") (pintype "input"))
    )
    (net (code "33") (name "PA14{slash}TCK") (class "Default")
      (node (ref "H11") (pin "1") (pinfunction "1_1") (pintype "input"))
      (node (ref "H2") (pin "9") (pinfunction "9_9") (pintype "input"))
      (node (ref "H7") (pin "1") (pinfunction "1_1") (pintype "input"))
      (node (ref "R21") (pin "2") (pinfunction "2_2") (pintype "input"))
    )
    (net (code "34") (name "PA15{slash}TDI") (class "Default")
      (node (ref "H11") (pin "2") (pinfunction "2_2") (pintype "input"))
      (node (ref "H2") (pin "5") (pinfunction "5_5") (pintype "input"))
      (node (ref "H7") (pin "2") (pinfunction "2_2") (pintype "input"))
      (node (ref "R19") (pin "1") (pinfunction "1_1") (pintype "input"))
    )
    (net (code "35") (name "PB0") (class "Default")
      (node (ref "H5") (pin "10") (pinfunction "10_10") (pintype "input"))
      (node (ref "H9") (pin "8") (pinfunction "8_8") (pintype "input"))
    )
    (net (code "36") (name "PB1") (class "Default")
      (node (ref "H5") (pin "11") (pinfunction "11_11") (pintype "input"))
      (node (ref "H9") (pin "9") (pinfunction "9_9") (pintype "input"))
    )
    (net (code "37") (name "PB2{slash}BOOT1") (class "Default")
      (node (ref "H5") (pin "12") (pinfunction "12_12") (pintype "input"))
      (node (ref "H9") (pin "10") (pinfunction "10_10") (pintype "input"))
      (node (ref "R23") (pin "1") (pinfunction "1_1") (pintype "input"))
    )
    (net (code "38") (name "PB3{slash}TDO") (class "Default")
      (node (ref "H11") (pin "7") (pinfunction "7_7") (pintype "input"))
      (node (ref "H2") (pin "13") (pinfunction "13_13") (pintype "input"))
      (node (ref "H7") (pin "7") (pinfunction "7_7") (pintype "input"))
      (node (ref "R17") (pin "1") (pinfunction "1_1") (pintype "input"))
    )
    (net (code "39") (name "PB4{slash}TRST") (class "Default")
      (node (ref "H11") (pin "8") (pinfunction "8_8") (pintype "input"))
      (node (ref "H2") (pin "3") (pinfunction "3_3") (pintype "input"))
      (node (ref "H7") (pin "8") (pinfunction "8_8") (pintype "input"))
      (node (ref "R20") (pin "1") (pinfunction "1_1") (pintype "input"))
    )
    (net (code "40") (name "PB5") (class "Default")
      (node (ref "H11") (pin "9") (pinfunction "9_9") (pintype "input"))
      (node (ref "H7") (pin "9") (pinfunction "9_9") (pintype "input"))
    )
    (net (code "41") (name "PB6") (class "Default")
      (node (ref "H11") (pin "10") (pinfunction "10_10") (pintype "input"))
      (node (ref "H7") (pin "10") (pinfunction "10_10") (pintype "input"))
    )
    (net (code "42") (name "PB7") (class "Default")
      (node (ref "H11") (pin "11") (pinfunction "11_11") (pintype "input"))
      (node (ref "H7") (pin "11") (pinfunction "11_11") (pintype "input"))
    )
    (net (code "43") (name "PB8") (class "Default")
      (node (ref "H11") (pin "12") (pinfunction "12_12") (pintype "input"))
      (node (ref "H7") (pin "13") (pinfunction "13_13") (pintype "input"))
    )
    (net (code "44") (name "PB9") (class "Default")
      (node (ref "H11") (pin "13") (pinfunction "13_13") (pintype "input"))
      (node (ref "H7") (pin "14") (pinfunction "14_14") (pintype "input"))
    )
    (net (code "45") (name "PB10") (class "Default")
      (node (ref "H5") (pin "13") (pinfunction "13_13") (pintype "input"))
      (node (ref "H9") (pin "11") (pinfunction "11_11") (pintype "input"))
    )
    (net (code "46") (name "PB11") (class "Default")
      (node (ref "H5") (pin "14") (pinfunction "14_14") (pintype "input"))
      (node (ref "H9") (pin "12") (pinfunction "12_12") (pintype "input"))
    )
    (net (code "47") (name "PB12") (class "Default")
      (node (ref "H10") (pin "1") (pinfunction "1_1") (pintype "input"))
      (node (ref "H6") (pin "1") (pinfunction "1_1") (pintype "input"))
    )
    (net (code "48") (name "PB13") (class "Default")
      (node (ref "H10") (pin "2") (pinfunction "2_2") (pintype "input"))
      (node (ref "H6") (pin "2") (pinfunction "2_2") (pintype "input"))
    )
    (net (code "49") (name "PB14") (class "Default")
      (node (ref "H10") (pin "3") (pinfunction "3_3") (pintype "input"))
      (node (ref "H6") (pin "3") (pinfunction "3_3") (pintype "input"))
    )
    (net (code "50") (name "PB15") (class "Default")
      (node (ref "H10") (pin "4") (pinfunction "4_4") (pintype "input"))
      (node (ref "H6") (pin "4") (pinfunction "4_4") (pintype "input"))
    )
    (net (code "51") (name "PC0") (class "Default")
      (node (ref "H4") (pin "8") (pinfunction "8_8") (pintype "input"))
      (node (ref "H8") (pin "6") (pinfunction "6_6") (pintype "input"))
    )
    (net (code "52") (name "PC1") (class "Default")
      (node (ref "H4") (pin "9") (pinfunction "9_9") (pintype "input"))
      (node (ref "H8") (pin "7") (pinfunction "7_7") (pintype "input"))
    )
    (net (code "53") (name "PC2") (class "Default")
      (node (ref "H4") (pin "10") (pinfunction "10_10") (pintype "input"))
      (node (ref "H8") (pin "8") (pinfunction "8_8") (pintype "input"))
    )
    (net (code "54") (name "PC3") (class "Default")
      (node (ref "H4") (pin "11") (pinfunction "11_11") (pintype "input"))
      (node (ref "H8") (pin "9") (pinfunction "9_9") (pintype "input"))
    )
    (net (code "55") (name "PC4") (class "Default")
      (node (ref "H5") (pin "8") (pinfunction "8_8") (pintype "input"))
      (node (ref "H9") (pin "6") (pinfunction "6_6") (pintype "input"))
    )
    (net (code "56") (name "PC5") (class "Default")
      (node (ref "H5") (pin "9") (pinfunction "9_9") (pintype "input"))
      (node (ref "H9") (pin "7") (pinfunction "7_7") (pintype "input"))
    )
    (net (code "57") (name "PC6") (class "Default")
      (node (ref "H10") (pin "5") (pinfunction "5_5") (pintype "input"))
      (node (ref "H6") (pin "5") (pinfunction "5_5") (pintype "input"))
    )
    (net (code "58") (name "PC7") (class "Default")
      (node (ref "H10") (pin "6") (pinfunction "6_6") (pintype "input"))
      (node (ref "H6") (pin "6") (pinfunction "6_6") (pintype "input"))
    )
    (net (code "59") (name "PC8") (class "Default")
      (node (ref "H10") (pin "7") (pinfunction "7_7") (pintype "input"))
      (node (ref "H6") (pin "7") (pinfunction "7_7") (pintype "input"))
    )
    (net (code "60") (name "PC9") (class "Default")
      (node (ref "H10") (pin "8") (pinfunction "8_8") (pintype "input"))
      (node (ref "H6") (pin "8") (pinfunction "8_8") (pintype "input"))
    )
    (net (code "61") (name "PC10") (class "Default")
      (node (ref "H11") (pin "3") (pinfunction "3_3") (pintype "input"))
      (node (ref "H7") (pin "3") (pinfunction "3_3") (pintype "input"))
    )
    (net (code "62") (name "PC11") (class "Default")
      (node (ref "H11") (pin "4") (pinfunction "4_4") (pintype "input"))
      (node (ref "H7") (pin "4") (pinfunction "4_4") (pintype "input"))
    )
    (net (code "63") (name "PC12") (class "Default")
      (node (ref "H11") (pin "5") (pinfunction "5_5") (pintype "input"))
      (node (ref "H7") (pin "5") (pinfunction "5_5") (pintype "input"))
    )
    (net (code "64") (name "PC13") (class "Default")
      (node (ref "H4") (pin "2") (pinfunction "2_2") (pintype "input"))
      (node (ref "H8") (pin "2") (pinfunction "2_2") (pintype "input"))
    )
    (net (code "65") (name "PC14") (class "Default")
      (node (ref "H4") (pin "3") (pinfunction "3_3") (pintype "input"))
      (node (ref "H8") (pin "3") (pinfunction "3_3") (pintype "input"))
    )
    (net (code "66") (name "PC15") (class "Default")
      (node (ref "H4") (pin "4") (pinfunction "4_4") (pintype "input"))
      (node (ref "H8") (pin "4") (pinfunction "4_4") (pintype "input"))
    )
    (net (code "67") (name "PD2") (class "Default")
      (node (ref "H11") (pin "6") (pinfunction "6_6") (pintype "input"))
      (node (ref "H7") (pin "6") (pinfunction "6_6") (pintype "input"))
    )
    (net (code "68") (name "RST") (class "Default")
      (node (ref "H2") (pin "15") (pinfunction "15_15") (pintype "input"))
      (node (ref "H4") (pin "7") (pinfunction "7_7") (pintype "input"))
      (node (ref "H8") (pin "5") (pinfunction "5_5") (pintype "input"))
    )
    (net (code "69") (name "VBAT") (class "Default")
      (node (ref "H4") (pin "1") (pinfunction "1_1") (pintype "input"))
      (node (ref "H8") (pin "1") (pinfunction "1_1") (pintype "input"))
      (node (ref "VBAT") (pin "2") (pinfunction "2_2") (pintype "unspecified"))
    )
    (net (code "70") (name "unconnected-(H2-Pad11)") (class "Default")
      (node (ref "H2") (pin "11") (pinfunction "11_11") (pintype "input"))
    )
    (net (code "71") (name "unconnected-(H2-Pad17)") (class "Default")
      (node (ref "H2") (pin "17") (pinfunction "17_17") (pintype "input"))
    )
    (net (code "72") (name "unconnected-(H2-Pad19)") (class "Default")
      (node (ref "H2") (pin "19") (pinfunction "19_19") (pintype "input"))
    )
  )
)
